# schematic.net
KiCad netlist of a schematic drawn in EAGLE
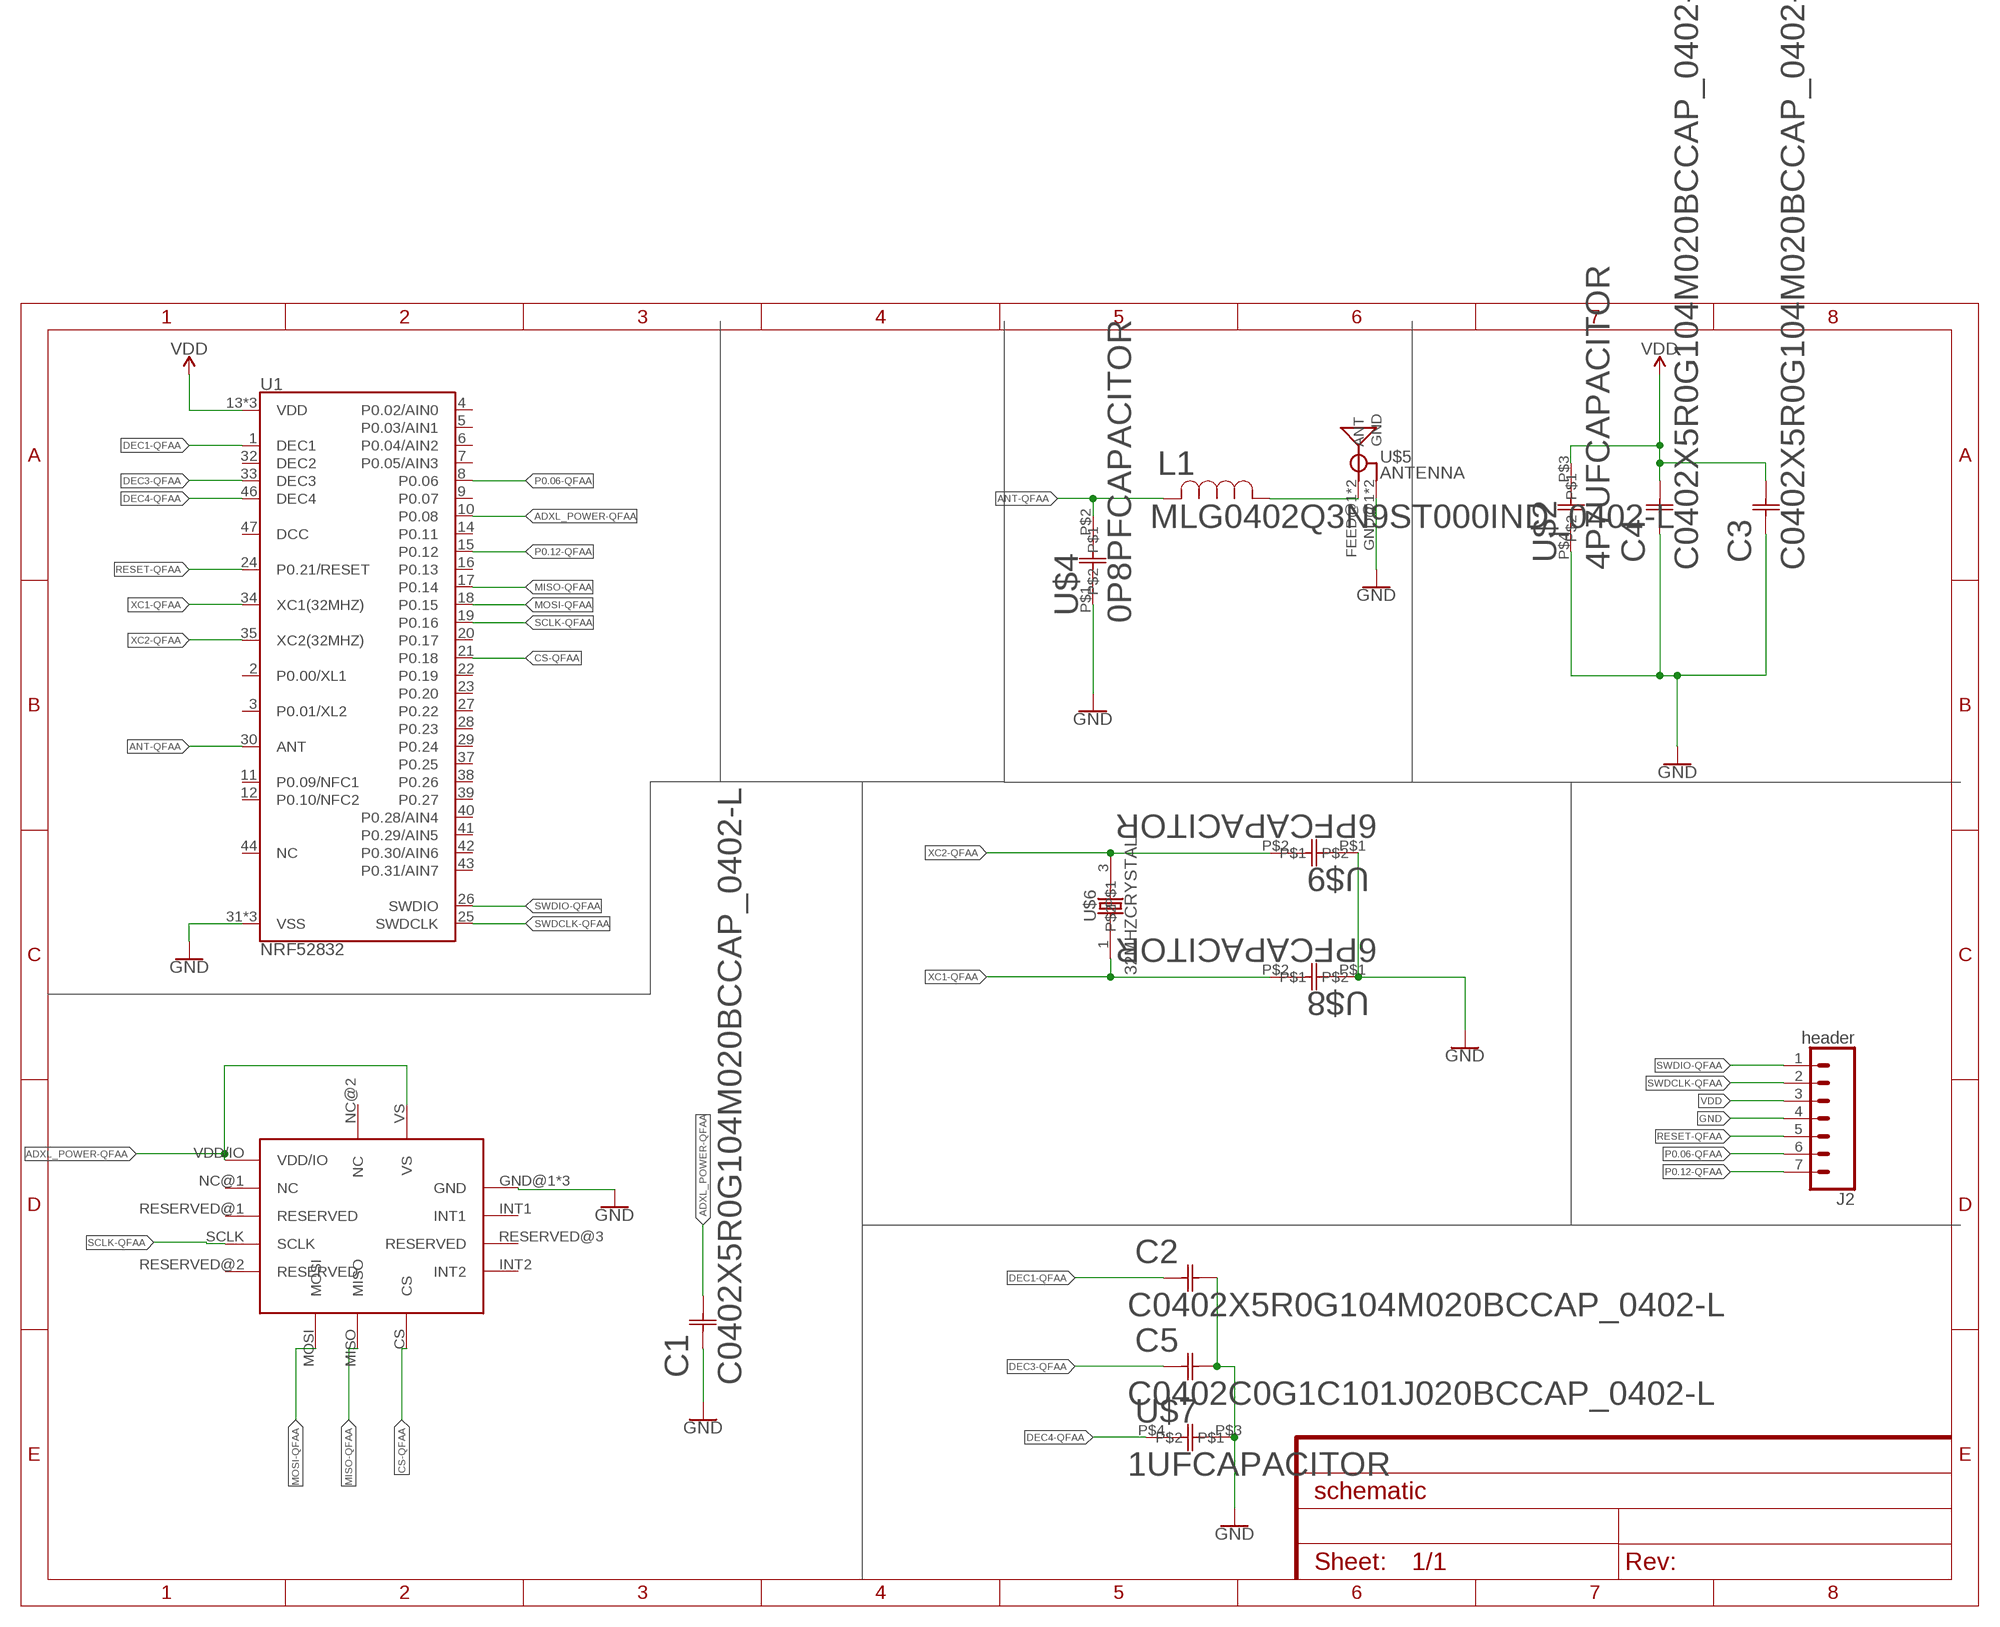
[diagram p0: schematic, sheet 1]

(export (version "E")
  (design (tool "Eeschema 10.0.6"))
  (components
    (comp (ref "C1")
      (value "C0402X5R0G104M020BCCAP_0402-L")
      (footprint "eagle-import:CAP_0402-L")
      (fields (field (name "MANUFACTURER_PART_NUMBER") "C0402C0G1C101J020BC"))
      (libsource (lib "eagle-import") (part "C0402X5R0G104M020BCCAP_0402-L"))
    )
    (comp (ref "C2")
      (value "C0402X5R0G104M020BCCAP_0402-L")
      (footprint "eagle-import:CAP_0402-L")
      (fields (field (name "MANUFACTURER_PART_NUMBER") "C0402C0G1C101J020BC"))
      (libsource (lib "eagle-import") (part "C0402X5R0G104M020BCCAP_0402-L"))
    )
    (comp (ref "C3")
      (value "C0402X5R0G104M020BCCAP_0402-L")
      (footprint "eagle-import:CAP_0402-L")
      (fields (field (name "MANUFACTURER_PART_NUMBER") "C0402C0G1C101J020BC"))
      (libsource (lib "eagle-import") (part "C0402X5R0G104M020BCCAP_0402-L"))
    )
    (comp (ref "C4")
      (value "C0402X5R0G104M020BCCAP_0402-L")
      (footprint "eagle-import:CAP_0402-L")
      (fields (field (name "MANUFACTURER_PART_NUMBER") "C0402C0G1C101J020BC"))
      (libsource (lib "eagle-import") (part "C0402X5R0G104M020BCCAP_0402-L"))
    )
    (comp (ref "C5")
      (value "C0402C0G1C101J020BCCAP_0402-L")
      (footprint "eagle-import:CAP_0402-L")
      (fields (field (name "MANUFACTURER_PART_NUMBER") "C0402C0G1C101J020BC"))
      (libsource (lib "eagle-import") (part "C0402C0G1C101J020BCCAP_0402-L"))
    )
    (comp (ref "J2")
      (value "header")
      (footprint "eagle-import:1X07")
      (libsource (lib "eagle-import") (part "CONN_07"))
    )
    (comp (ref "L1")
      (value "MLG0402Q3N9ST000IND_0402-L")
      (footprint "eagle-import:IND_0402-L")
      (fields (field (name "MANUFACTURER_PART_NUMBER") "MLG0402Q3N9ST000"))
      (libsource (lib "eagle-import") (part "MLG0402Q3N9ST000IND_0402-L"))
    )
    (comp (ref "U$1")
      (value "ADXL362")
      (footprint "eagle-import:TFLGA-16_3.3MMX3.1MM")
      (libsource (lib "eagle-import") (part "ADXL362"))
    )
    (comp (ref "U$2")
      (value "4P7UFCAPACITOR")
      (footprint "eagle-import:4P7UFCAPACITOR")
      (libsource (lib "eagle-import") (part "4P7UFCAPACITOR"))
    )
    (comp (ref "U$4")
      (value "0P8PFCAPACITOR")
      (footprint "eagle-import:0P8PFCAPACITOR")
      (libsource (lib "eagle-import") (part "0P8PFCAPACITOR"))
    )
    (comp (ref "U$5")
      (value "ANTENNA")
      (footprint "eagle-import:ANTENNA_FOOTPRINT")
      (libsource (lib "eagle-import") (part "ANTENNA"))
    )
    (comp (ref "U$6")
      (value "32MHZCRYSTAL")
      (footprint "eagle-import:32MHZCRYSTAL")
      (libsource (lib "eagle-import") (part "32MHZCRYSTAL"))
    )
    (comp (ref "U$7")
      (value "1UFCAPACITOR")
      (footprint "eagle-import:1UFCAPACITOR")
      (libsource (lib "eagle-import") (part "1UFCAPACITOR"))
    )
    (comp (ref "U$8")
      (value "6PFCAPACITOR")
      (footprint "eagle-import:6PFCAPACITOR")
      (libsource (lib "eagle-import") (part "6PFCAPACITOR"))
    )
    (comp (ref "U$9")
      (value "6PFCAPACITOR")
      (footprint "eagle-import:6PFCAPACITOR")
      (libsource (lib "eagle-import") (part "6PFCAPACITOR"))
    )
    (comp (ref "U1")
      (value "NRF52832")
      (footprint "eagle-import:QFN48-6X6MM")
      (libsource (lib "eagle-import") (part "NRF52832"))
    )
  )
  (nets
    (net (code "1") (name "ADXL_POWER-QFAA") (class "Default")
      (node (ref "C1") (pin "2") (pinfunction "22_2") (pintype "passive"))
      (node (ref "U$1") (pin "VDD/IO") (pinfunction "VDD/IO_VDD/IO") (pintype "bidirectional"))
      (node (ref "U$1") (pin "VS") (pinfunction "VS_VS") (pintype "bidirectional"))
      (node (ref "U1") (pin "10") (pinfunction "P0.08_10") (pintype "bidirectional"))
    )
    (net (code "2") (name "ANT-QFAA") (class "Default")
      (node (ref "L1") (pin "2") (pinfunction "2_2") (pintype "passive"))
      (node (ref "U$4") (pin "P$2") (pinfunction "P$2_P$2") (pintype "bidirectional"))
      (node (ref "U1") (pin "30") (pinfunction "ANT_30") (pintype "bidirectional"))
    )
    (net (code "3") (name "CS-QFAA") (class "Default")
      (node (ref "U$1") (pin "CS") (pinfunction "CS_CS") (pintype "bidirectional"))
      (node (ref "U1") (pin "21") (pinfunction "P0.18_21") (pintype "bidirectional"))
    )
    (net (code "4") (name "DEC1-QFAA") (class "Default")
      (node (ref "C2") (pin "1") (pinfunction "11_1") (pintype "passive"))
      (node (ref "U1") (pin "1") (pinfunction "DEC1_1") (pintype "bidirectional"))
    )
    (net (code "5") (name "DEC3-QFAA") (class "Default")
      (node (ref "C5") (pin "1") (pinfunction "11_1") (pintype "passive"))
      (node (ref "U1") (pin "33") (pinfunction "DEC3_33") (pintype "bidirectional"))
    )
    (net (code "6") (name "DEC4-QFAA") (class "Default")
      (node (ref "U$7") (pin "P$4") (pinfunction "P$1_P$4") (pintype "bidirectional"))
      (node (ref "U1") (pin "46") (pinfunction "DEC4_46") (pintype "bidirectional"))
    )
    (net (code "7") (name "GND") (class "Default")
      (node (ref "C1") (pin "1") (pinfunction "11_1") (pintype "passive"))
      (node (ref "C2") (pin "2") (pinfunction "22_2") (pintype "passive"))
      (node (ref "C3") (pin "1") (pinfunction "11_1") (pintype "passive"))
      (node (ref "C4") (pin "1") (pinfunction "11_1") (pintype "passive"))
      (node (ref "C5") (pin "2") (pinfunction "22_2") (pintype "passive"))
      (node (ref "J2") (pin "4") (pinfunction "4_4") (pintype "passive"))
      (node (ref "U$1") (pin "GND@1") (pinfunction "GND_GND@1") (pintype "bidirectional"))
      (node (ref "U$1") (pin "GND@2") (pinfunction "GND_GND@2") (pintype "bidirectional"))
      (node (ref "U$1") (pin "GND@3") (pinfunction "GND_GND@3") (pintype "bidirectional"))
      (node (ref "U$2") (pin "P$4") (pinfunction "P$1_P$4") (pintype "bidirectional"))
      (node (ref "U$4") (pin "P$1") (pinfunction "P$1_P$1") (pintype "bidirectional"))
      (node (ref "U$5") (pin "GND@1") (pinfunction "GND_GND@1") (pintype "bidirectional"))
      (node (ref "U$5") (pin "GND@2") (pinfunction "GND_GND@2") (pintype "bidirectional"))
      (node (ref "U$7") (pin "P$3") (pinfunction "P$2_P$3") (pintype "bidirectional"))
      (node (ref "U$8") (pin "P$1") (pinfunction "P$1_P$1") (pintype "bidirectional"))
      (node (ref "U$9") (pin "P$1") (pinfunction "P$1_P$1") (pintype "bidirectional"))
      (node (ref "U1") (pin "31") (pinfunction "VSS_31") (pintype "bidirectional"))
      (node (ref "U1") (pin "45") (pinfunction "VSS_45") (pintype "bidirectional"))
      (node (ref "U1") (pin "EP") (pinfunction "VSS_EP") (pintype "bidirectional"))
    )
    (net (code "8") (name "MISO-QFAA") (class "Default")
      (node (ref "U$1") (pin "MISO") (pinfunction "MISO_MISO") (pintype "bidirectional"))
      (node (ref "U1") (pin "17") (pinfunction "P0.14_17") (pintype "bidirectional"))
    )
    (net (code "9") (name "MOSI-QFAA") (class "Default")
      (node (ref "U$1") (pin "MOSI") (pinfunction "MOSI_MOSI") (pintype "bidirectional"))
      (node (ref "U1") (pin "18") (pinfunction "P0.15_18") (pintype "bidirectional"))
    )
    (net (code "10") (name "Net-(L1-Pad1)") (class "Default")
      (node (ref "L1") (pin "1") (pinfunction "1_1") (pintype "passive"))
      (node (ref "U$5") (pin "FEED@1") (pinfunction "ANT_FEED@1") (pintype "bidirectional"))
      (node (ref "U$5") (pin "FEED@2") (pinfunction "ANT_FEED@2") (pintype "bidirectional"))
    )
    (net (code "11") (name "P0.06-QFAA") (class "Default")
      (node (ref "J2") (pin "6") (pinfunction "6_6") (pintype "passive"))
      (node (ref "U1") (pin "8") (pinfunction "P0.06_8") (pintype "bidirectional"))
    )
    (net (code "12") (name "P0.12-QFAA") (class "Default")
      (node (ref "J2") (pin "7") (pinfunction "7_7") (pintype "passive"))
      (node (ref "U1") (pin "15") (pinfunction "P0.12_15") (pintype "bidirectional"))
    )
    (net (code "13") (name "RESET-QFAA") (class "Default")
      (node (ref "J2") (pin "5") (pinfunction "5_5") (pintype "passive"))
      (node (ref "U1") (pin "24") (pinfunction "P0.21/RESET_24") (pintype "bidirectional"))
    )
    (net (code "14") (name "SCLK-QFAA") (class "Default")
      (node (ref "U$1") (pin "SCLK") (pinfunction "SCLK_SCLK") (pintype "bidirectional"))
      (node (ref "U1") (pin "19") (pinfunction "P0.16_19") (pintype "bidirectional"))
    )
    (net (code "15") (name "SWDCLK-QFAA") (class "Default")
      (node (ref "J2") (pin "2") (pinfunction "2_2") (pintype "passive"))
      (node (ref "U1") (pin "25") (pinfunction "SWDCLK_25") (pintype "bidirectional"))
    )
    (net (code "16") (name "SWDIO-QFAA") (class "Default")
      (node (ref "J2") (pin "1") (pinfunction "1_1") (pintype "passive"))
      (node (ref "U1") (pin "26") (pinfunction "SWDIO_26") (pintype "bidirectional"))
    )
    (net (code "17") (name "VDD") (class "Default")
      (node (ref "C3") (pin "2") (pinfunction "22_2") (pintype "passive"))
      (node (ref "C4") (pin "2") (pinfunction "22_2") (pintype "passive"))
      (node (ref "J2") (pin "3") (pinfunction "3_3") (pintype "passive"))
      (node (ref "U$2") (pin "P$3") (pinfunction "P$2_P$3") (pintype "bidirectional"))
      (node (ref "U1") (pin "13") (pinfunction "VDD_13") (pintype "bidirectional"))
      (node (ref "U1") (pin "36") (pinfunction "VDD_36") (pintype "bidirectional"))
      (node (ref "U1") (pin "48") (pinfunction "VDD_48") (pintype "bidirectional"))
    )
    (net (code "18") (name "XC1-QFAA") (class "Default")
      (node (ref "U$6") (pin "1") (pinfunction "P$1_1") (pintype "bidirectional"))
      (node (ref "U$8") (pin "P$2") (pinfunction "P$2_P$2") (pintype "bidirectional"))
      (node (ref "U1") (pin "34") (pinfunction "XC1(32MHZ)_34") (pintype "bidirectional"))
    )
    (net (code "19") (name "XC2-QFAA") (class "Default")
      (node (ref "U$6") (pin "3") (pinfunction "P$2_3") (pintype "bidirectional"))
      (node (ref "U$9") (pin "P$2") (pinfunction "P$2_P$2") (pintype "bidirectional"))
      (node (ref "U1") (pin "35") (pinfunction "XC2(32MHZ)_35") (pintype "bidirectional"))
    )
    (net (code "20") (name "unconnected-(U$1-NC-PadNC@1)") (class "Default")
      (node (ref "U$1") (pin "NC@1") (pinfunction "NC_NC@1") (pintype "bidirectional"))
    )
    (net (code "21") (name "unconnected-(U$1-NC-PadNC@2)") (class "Default")
      (node (ref "U$1") (pin "NC@2") (pinfunction "NC_NC@2") (pintype "bidirectional"))
    )
    (net (code "22") (name "unconnected-(U$1-PadINT1)") (class "Default")
      (node (ref "U$1") (pin "INT1") (pinfunction "INT1_INT1") (pintype "bidirectional"))
    )
    (net (code "23") (name "unconnected-(U$1-PadINT2)") (class "Default")
      (node (ref "U$1") (pin "INT2") (pinfunction "INT2_INT2") (pintype "bidirectional"))
    )
    (net (code "24") (name "unconnected-(U$1-RESERVED-PadRESERVED@1)") (class "Default")
      (node (ref "U$1") (pin "RESERVED@1") (pinfunction "RESERVED_RESERVED@1") (pintype "bidirectional"))
    )
    (net (code "25") (name "unconnected-(U$1-RESERVED-PadRESERVED@2)") (class "Default")
      (node (ref "U$1") (pin "RESERVED@2") (pinfunction "RESERVED_RESERVED@2") (pintype "bidirectional"))
    )
    (net (code "26") (name "unconnected-(U$1-RESERVED-PadRESERVED@3)") (class "Default")
      (node (ref "U$1") (pin "RESERVED@3") (pinfunction "RESERVED_RESERVED@3") (pintype "bidirectional"))
    )
    (net (code "27") (name "unconnected-(U1-DCC-Pad47)") (class "Default")
      (node (ref "U1") (pin "47") (pinfunction "DCC_47") (pintype "bidirectional"))
    )
    (net (code "28") (name "unconnected-(U1-DEC2-Pad32)") (class "Default")
      (node (ref "U1") (pin "32") (pinfunction "DEC2_32") (pintype "bidirectional"))
    )
    (net (code "29") (name "unconnected-(U1-NC-Pad44)") (class "Default")
      (node (ref "U1") (pin "44") (pinfunction "NC_44") (pintype "bidirectional"))
    )
    (net (code "30") (name "unconnected-(U1-P0.00{slash}XL1-Pad2)") (class "Default")
      (node (ref "U1") (pin "2") (pinfunction "P0.00/XL1_2") (pintype "bidirectional"))
    )
    (net (code "31") (name "unconnected-(U1-P0.01{slash}XL2-Pad3)") (class "Default")
      (node (ref "U1") (pin "3") (pinfunction "P0.01/XL2_3") (pintype "bidirectional"))
    )
    (net (code "32") (name "unconnected-(U1-P0.02{slash}AIN0-Pad4)") (class "Default")
      (node (ref "U1") (pin "4") (pinfunction "P0.02/AIN0_4") (pintype "bidirectional"))
    )
    (net (code "33") (name "unconnected-(U1-P0.03{slash}AIN1-Pad5)") (class "Default")
      (node (ref "U1") (pin "5") (pinfunction "P0.03/AIN1_5") (pintype "bidirectional"))
    )
    (net (code "34") (name "unconnected-(U1-P0.04{slash}AIN2-Pad6)") (class "Default")
      (node (ref "U1") (pin "6") (pinfunction "P0.04/AIN2_6") (pintype "bidirectional"))
    )
    (net (code "35") (name "unconnected-(U1-P0.05{slash}AIN3-Pad7)") (class "Default")
      (node (ref "U1") (pin "7") (pinfunction "P0.05/AIN3_7") (pintype "bidirectional"))
    )
    (net (code "36") (name "unconnected-(U1-P0.07-Pad9)") (class "Default")
      (node (ref "U1") (pin "9") (pinfunction "P0.07_9") (pintype "bidirectional"))
    )
    (net (code "37") (name "unconnected-(U1-P0.09{slash}NFC1-Pad11)") (class "Default")
      (node (ref "U1") (pin "11") (pinfunction "P0.09/NFC1_11") (pintype "bidirectional"))
    )
    (net (code "38") (name "unconnected-(U1-P0.10{slash}NFC2-Pad12)") (class "Default")
      (node (ref "U1") (pin "12") (pinfunction "P0.10/NFC2_12") (pintype "bidirectional"))
    )
    (net (code "39") (name "unconnected-(U1-P0.11-Pad14)") (class "Default")
      (node (ref "U1") (pin "14") (pinfunction "P0.11_14") (pintype "bidirectional"))
    )
    (net (code "40") (name "unconnected-(U1-P0.13-Pad16)") (class "Default")
      (node (ref "U1") (pin "16") (pinfunction "P0.13_16") (pintype "bidirectional"))
    )
    (net (code "41") (name "unconnected-(U1-P0.17-Pad20)") (class "Default")
      (node (ref "U1") (pin "20") (pinfunction "P0.17_20") (pintype "bidirectional"))
    )
    (net (code "42") (name "unconnected-(U1-P0.19-Pad22)") (class "Default")
      (node (ref "U1") (pin "22") (pinfunction "P0.19_22") (pintype "bidirectional"))
    )
    (net (code "43") (name "unconnected-(U1-P0.20-Pad23)") (class "Default")
      (node (ref "U1") (pin "23") (pinfunction "P0.20_23") (pintype "bidirectional"))
    )
    (net (code "44") (name "unconnected-(U1-P0.22-Pad27)") (class "Default")
      (node (ref "U1") (pin "27") (pinfunction "P0.22_27") (pintype "bidirectional"))
    )
    (net (code "45") (name "unconnected-(U1-P0.23-Pad28)") (class "Default")
      (node (ref "U1") (pin "28") (pinfunction "P0.23_28") (pintype "bidirectional"))
    )
    (net (code "46") (name "unconnected-(U1-P0.24-Pad29)") (class "Default")
      (node (ref "U1") (pin "29") (pinfunction "P0.24_29") (pintype "bidirectional"))
    )
    (net (code "47") (name "unconnected-(U1-P0.25-Pad37)") (class "Default")
      (node (ref "U1") (pin "37") (pinfunction "P0.25_37") (pintype "bidirectional"))
    )
    (net (code "48") (name "unconnected-(U1-P0.26-Pad38)") (class "Default")
      (node (ref "U1") (pin "38") (pinfunction "P0.26_38") (pintype "bidirectional"))
    )
    (net (code "49") (name "unconnected-(U1-P0.27-Pad39)") (class "Default")
      (node (ref "U1") (pin "39") (pinfunction "P0.27_39") (pintype "bidirectional"))
    )
    (net (code "50") (name "unconnected-(U1-P0.28{slash}AIN4-Pad40)") (class "Default")
      (node (ref "U1") (pin "40") (pinfunction "P0.28/AIN4_40") (pintype "bidirectional"))
    )
    (net (code "51") (name "unconnected-(U1-P0.29{slash}AIN5-Pad41)") (class "Default")
      (node (ref "U1") (pin "41") (pinfunction "P0.29/AIN5_41") (pintype "bidirectional"))
    )
    (net (code "52") (name "unconnected-(U1-P0.30{slash}AIN6-Pad42)") (class "Default")
      (node (ref "U1") (pin "42") (pinfunction "P0.30/AIN6_42") (pintype "bidirectional"))
    )
    (net (code "53") (name "unconnected-(U1-P0.31{slash}AIN7-Pad43)") (class "Default")
      (node (ref "U1") (pin "43") (pinfunction "P0.31/AIN7_43") (pintype "bidirectional"))
    )
  )
)
